# MAIN.net
KiCad netlist of a schematic drawn in Altium Designer
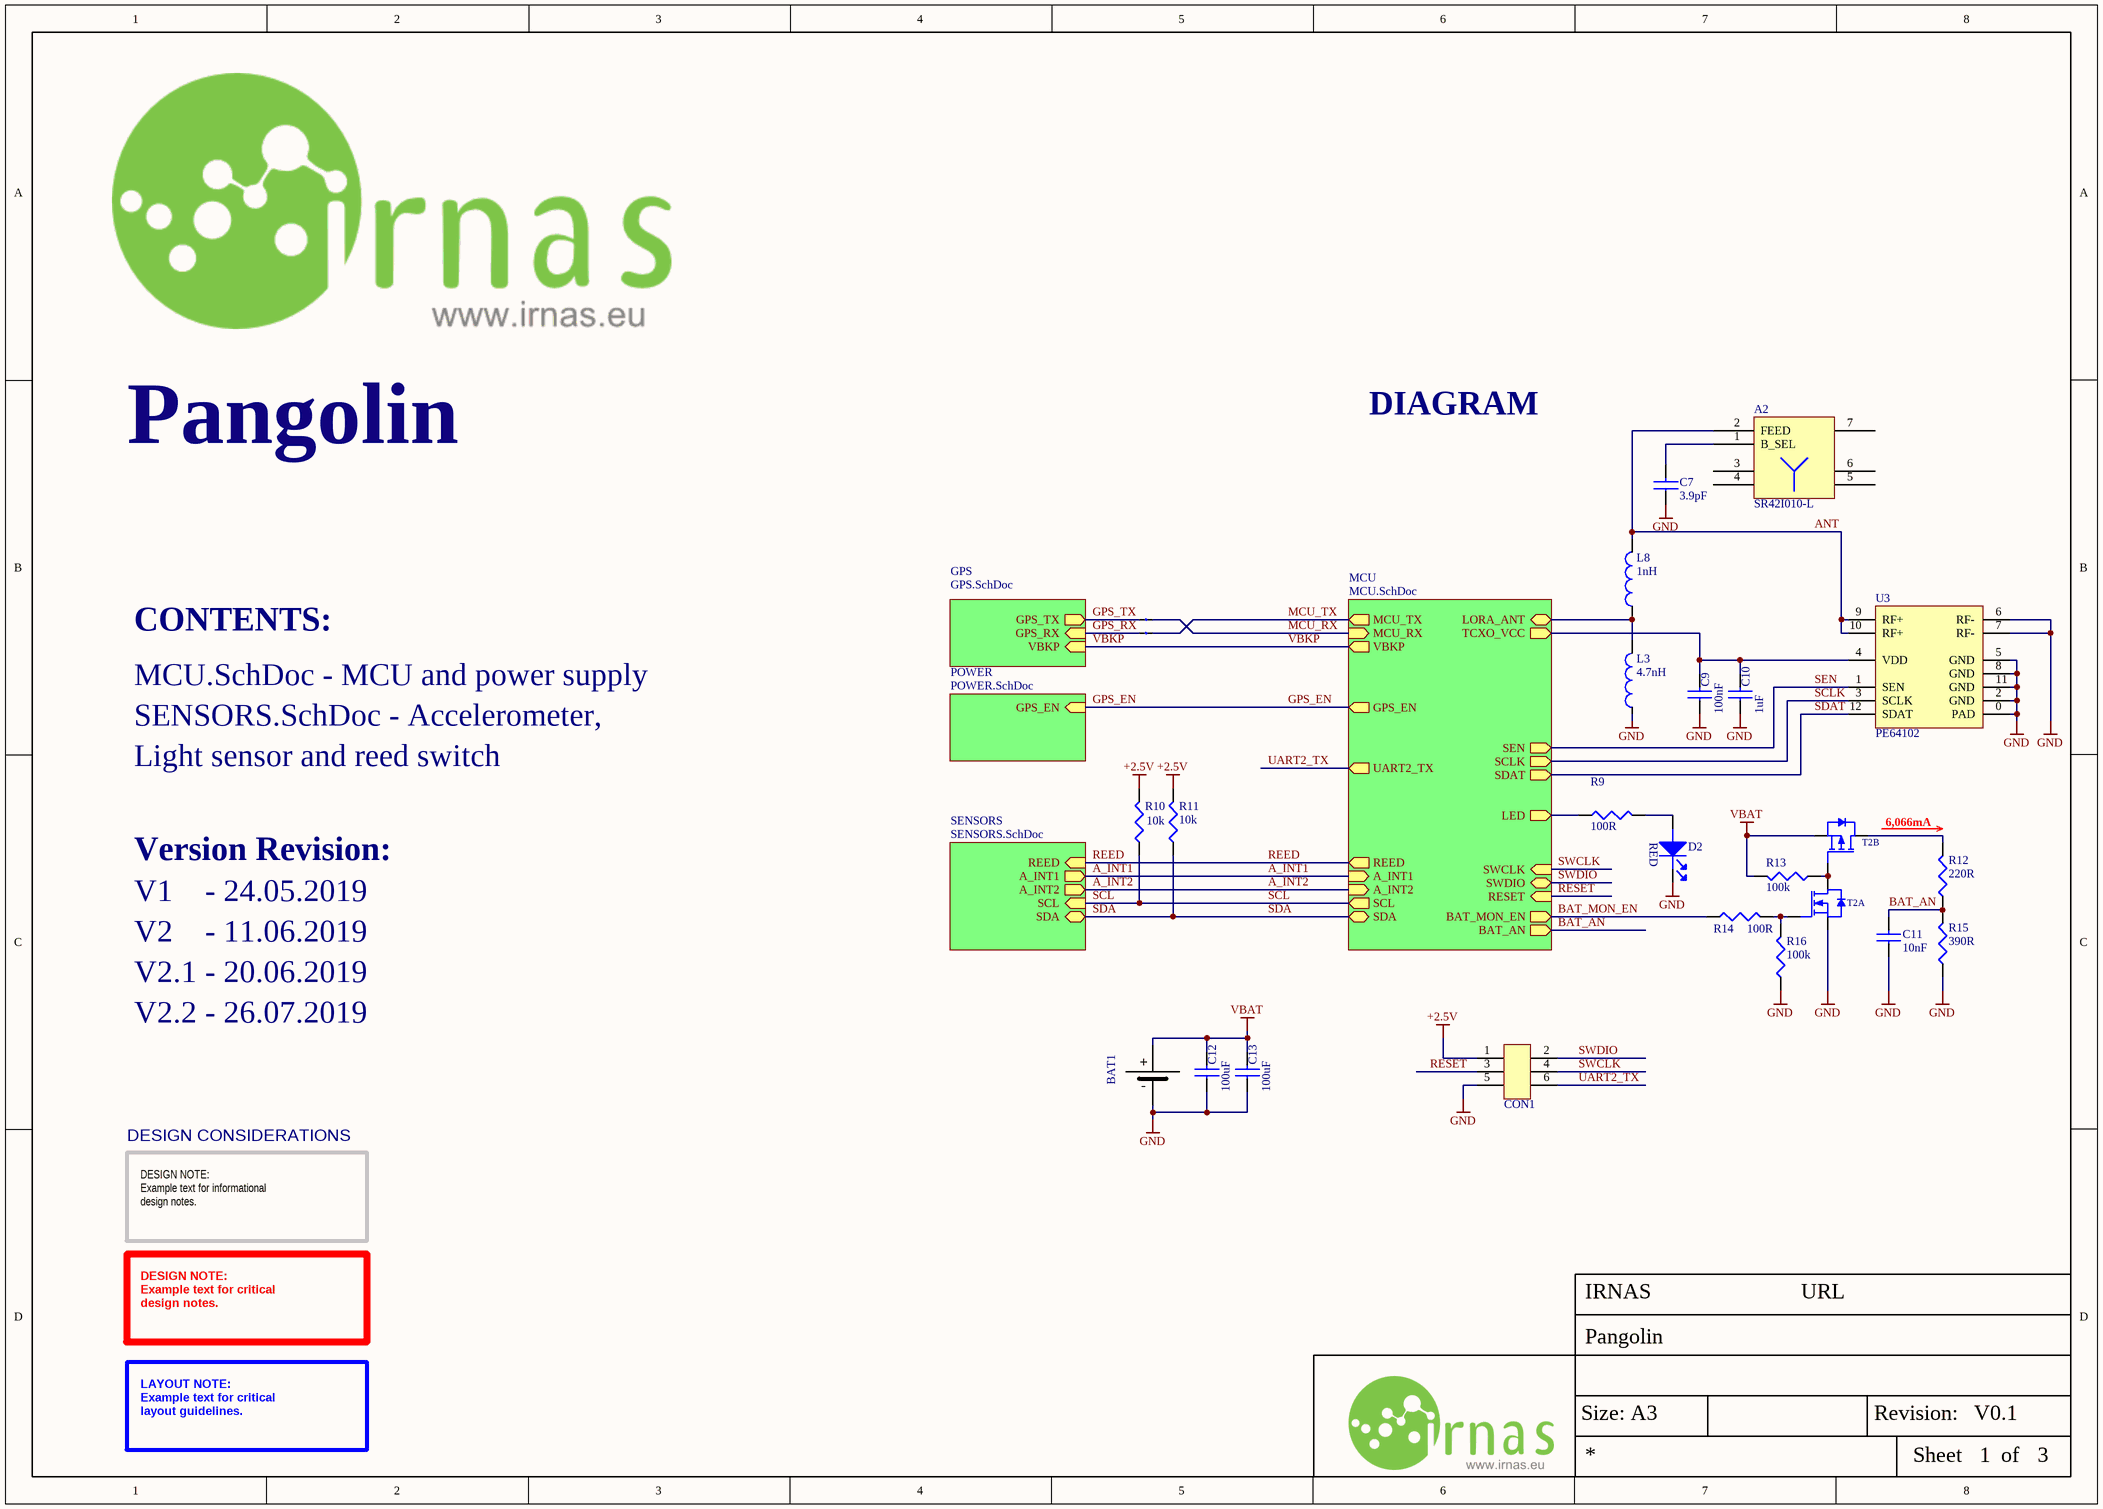
[diagram p0: MAIN.SchDoc]

(export (version "E")
  (design (tool "Eeschema 10.0.6"))
  (components
    (comp (ref "A2")
      (value "SR42I010-L")
      (footprint "SR42I010-L")
      (description "Antenna SMD -4dBi Gain 870MHz/928MHz Automotive 7-Pin SMD T/R")
      (fields (field (name "MANUFACTURER") "Antenova") (field (name "MANUFACTURER PART NUMBER") "SR42I010-R"))
      (libsource (lib "Passive") (part "ANT - SR42I010-L"))
    )
    (comp (ref "BAT1")
      (value "SAFT LS 14250PFR")
      (footprint "SAFT LS 14250PFR")
      (description "Battery: lithium; 3.6V; 1/2AA; 3pin,positive pole: 1pin; 1200mAh")
      (libsource (lib "Mechanical") (part "BAT - SAFT LS 14250PFR"))
    )
    (comp (ref "C7")
      (value "3.9pF")
      (footprint "CAP0402")
      (description "3.9 pF, 50 V, 0402 [1005 Metric], ± 0.25pF, NP0")
      (fields
        (field (name "MANUFACTURER") "KEMET")
        (field (name "MANUFACTURER PART NUMBER") "MC0402N3R9C500CT")
      )
      (libsource (lib "Passive") (part "C - 3.9pF/0402"))
    )
    (comp (ref "C9")
      (value "100nF")
      (footprint "CAP0402")
      (fields
        (field (name "MANUFACTURER") "Multicomp")
        (field (name "MANUFACTURER PART NUMBER") "MC0402X104J160CT")
        (field (name "TOLERANCE") "5%")
      )
      (libsource (lib "Passive") (part "C - 100nF/0402"))
    )
    (comp (ref "C10")
      (value "1uF")
      (footprint "CAP0402")
      (description "CAP CER 1UF 10V 20% X5R 0402")
      (fields
        (field (name "MANUFACTURER") "Murata")
        (field (name "MANUFACTURER PART NUMBER") "GRM155R61A105ME15D")
      )
      (libsource (lib "Passive") (part "C - 1uF/0402"))
    )
    (comp (ref "C11")
      (value "10nF")
      (footprint "CAP0402")
      (description "CAP CER 10000PF 16V X7R 0402")
      (fields
        (field (name "MANUFACTURER") "Murata")
        (field (name "MANUFACTURER PART NUMBER") "GRM155R71C103KA01D")
      )
      (libsource (lib "Passive") (part "C - 10nF/0402"))
    )
    (comp (ref "C12")
      (value "100uF")
      (footprint "CAP0805")
      (description "Multilayer Ceramic Capacitors MLCC - SMD/SMT 0805 100uF 4volts *Derate Voltage/Temp")
      (fields
        (field (name "MANUFACTURER") "Murata")
        (field (name "MANUFACTURER PART NUMBER") "GRM21BR60G107ME15L")
      )
      (libsource (lib "Passive") (part "C - 100uF/0805"))
    )
    (comp (ref "C13")
      (value "100uF")
      (footprint "CAP0805")
      (description "Multilayer Ceramic Capacitors MLCC - SMD/SMT 0805 100uF 4volts *Derate Voltage/Temp")
      (fields
        (field (name "MANUFACTURER") "Murata")
        (field (name "MANUFACTURER PART NUMBER") "GRM21BR60G107ME15L")
      )
      (libsource (lib "Passive") (part "C - 100uF/0805"))
    )
    (comp (ref "CON1")
      (value "Tag connect")
      (footprint "TC2030-IDC-NL")
      (libsource (lib "Connectors") (part "tag connecot 6 pin"))
    )
    (comp (ref "D2")
      (value "LED RED")
      (footprint "LED0603")
      (description "BROADCOM LIMITED - HSMS-C190 - LED, RED, 10MCD, 626NM")
      (fields
        (field (name "MANUFACTURER") "BROADCOM LIMITED")
        (field (name "MANUFACTURER PART NUMBER") "HSMS-C190")
      )
      (libsource (lib "Active") (part "LED - LED RED"))
    )
    (comp (ref "L3")
      (value "4.7nH")
      (footprint "IND0402")
      (description "Inductor RF Chip Multi-Layer 4.3nH 0.3nH 100MHz 8Q-Factor Air 300mA 210mOhm DCR 0402 Paper T/R")
      (fields
        (field (name "MANUFACTURER") "Murata")
        (field (name "MANUFACTURER PART NUMBER") "LQG15HN4N3S02D")
      )
      (libsource (lib "Passive") (part "L - 4.3nH/0402"))
    )
    (comp (ref "L8")
      (value "1nH")
      (footprint "IND0402")
      (description "Inductor RF Chip Multi-Layer 4.3nH 0.3nH 100MHz 8Q-Factor Air 300mA 210mOhm DCR 0402 Paper T/R")
      (fields
        (field (name "MANUFACTURER") "Murata")
        (field (name "MANUFACTURER PART NUMBER") "LQG15HN4N3S02D")
      )
      (libsource (lib "Passive") (part "L - 4.3nH/0402"))
    )
    (comp (ref "NT1")
      (value "~")
      (footprint "2 PIN STARPOINT")
      (description "Starpoint")
      (libsource (lib "Passive") (part "NetTie"))
    )
    (comp (ref "NT2")
      (value "~")
      (footprint "2 PIN STARPOINT")
      (description "Starpoint")
      (libsource (lib "Passive") (part "NetTie"))
    )
    (comp (ref "R9")
      (value "100R")
      (footprint "RES0402")
      (fields
        (field (name "MANUFACTURER") "Multicomp")
        (field (name "MANUFACTURER PART NUMBER") "MCMR04X1000FTL")
        (field (name "TOLERANCE") "1%")
      )
      (libsource (lib "Passive") (part "R - 100R/0402"))
    )
    (comp (ref "R10")
      (value "10k")
      (footprint "RES0402")
      (fields
        (field (name "MANUFACTURER") "Multicomp")
        (field (name "MANUFACTURER PART NUMBER") "MCWR04X1002FTL")
        (field (name "TOLERANCE") "1%")
      )
      (libsource (lib "Passive") (part "R - 10k/0402"))
    )
    (comp (ref "R11")
      (value "10k")
      (footprint "RES0402")
      (fields
        (field (name "MANUFACTURER") "Multicomp")
        (field (name "MANUFACTURER PART NUMBER") "MCWR04X1002FTL")
        (field (name "TOLERANCE") "1%")
      )
      (libsource (lib "Passive") (part "R - 10k/0402"))
    )
    (comp (ref "R12")
      (value "220R")
      (footprint "RES0402")
      (description "SMD Chip Resistor, 0402 [1005 Metric], 220 ohm, CRCW e3 Series, 50 V, Thick Film, 63 mW")
      (fields (field (name "MANUFACTURER") "Multicomp") (field (name "IRNAS PART NO.") "/"))
      (libsource (lib "Passive") (part "R - 220R/0402"))
    )
    (comp (ref "R13")
      (value "100k")
      (footprint "RES0402")
      (description "MULTICOMP   MCWR04X1003FTL   RES, THICK FILM, 100KOHM, 1%, 0.0625W")
      (fields
        (field (name "MANUFACTURER") "Multicomp")
        (field (name "MANUFACTURER PART NUMBER") "MCWR04X1003FTL")
      )
      (libsource (lib "Passive") (part "R - 100k/0402"))
    )
    (comp (ref "R14")
      (value "100R")
      (footprint "RES0402")
      (fields
        (field (name "MANUFACTURER") "Multicomp")
        (field (name "MANUFACTURER PART NUMBER") "MCMR04X1000FTL")
        (field (name "TOLERANCE") "1%")
      )
      (libsource (lib "Passive") (part "R - 100R/0402"))
    )
    (comp (ref "R15")
      (value "390R")
      (footprint "RES0402")
      (description "SMD Chip Resistor, 0402 [1005 Metric], 390 ohm, MCWR Series, 50 V, Thick Film, 62.5 mW")
      (fields (field (name "MANUFACTURER") "Multicomp") (field (name "IRNAS PART NO.") "/"))
      (libsource (lib "Passive") (part "R - 390R/0402"))
    )
    (comp (ref "R16")
      (value "100k")
      (footprint "RES0402")
      (description "MULTICOMP   MCWR04X1003FTL   RES, THICK FILM, 100KOHM, 1%, 0.0625W")
      (fields
        (field (name "MANUFACTURER") "Multicomp")
        (field (name "MANUFACTURER PART NUMBER") "MCWR04X1003FTL")
      )
      (libsource (lib "Passive") (part "R - 100k/0402"))
    )
    (comp (ref "T2")
      (value "VT6M1T2CR")
      (footprint "VMT6")
      (description "Dual MOSFET, N and P Channel, 100 mA, 20 V, 2.5 ohm, 4.5 V, 1 V")
      (fields (field (name "AUTHOR") "Ciril Golob"))
      (libsource (lib "Active") (part "T_M - VT6M1T2CR"))
    )
    (comp (ref "U3")
      (value "PE64102")
      (footprint "QFN-12")
      (description "RF IC Digitally Tunable Capacitor General Purpose 100MHz ~ 3GHz SPI Interface 12-QFN (2x2)")
      (fields (field (name "MANUFACTURER") "u-blox") (field (name "MANUFACTURER PART NUMBER") "MAX-M8Q-0"))
      (libsource (lib "Active") (part "RF - PE64102"))
    )
  )
  (nets
    (net (code "1") (name "+2.5V") (class "Default")
      (node (ref "CON1") (pin "1") (pinfunction "1_1") (pintype "open_collector"))
      (node (ref "R10") (pin "2") (pinfunction "2_2") (pintype "passive"))
      (node (ref "R11") (pin "2") (pinfunction "2_2") (pintype "passive"))
    )
    (net (code "2") (name "/ANT") (class "Default")
      (node (ref "A2") (pin "2") (pinfunction "FEED_2") (pintype "passive"))
      (node (ref "L8") (pin "2") (pinfunction "2_2") (pintype "passive"))
      (node (ref "U3") (pin "10") (pinfunction "RF+_10") (pintype "passive"))
      (node (ref "U3") (pin "9") (pinfunction "RF+_9") (pintype "passive"))
    )
    (net (code "5") (name "/BAT_AN") (class "Default")
      (node (ref "C11") (pin "2") (pinfunction "2_2") (pintype "passive"))
      (node (ref "R12") (pin "1") (pinfunction "1_1") (pintype "passive"))
      (node (ref "R15") (pin "2") (pinfunction "2_2") (pintype "passive"))
    )
    (net (code "6") (name "/BAT_MON_EN") (class "Default")
      (node (ref "R14") (pin "1") (pinfunction "1_1") (pintype "passive"))
    )
    (net (code "8") (name "/GPS_RX") (class "Default") (node (ref "NT2") (pin "1") (pintype "passive")))
    (net (code "9") (name "/GPS_TX") (class "Default") (node (ref "NT1") (pin "1") (pintype "passive")))
    (net (code "10") (name "/LED") (class "Default")
      (node (ref "R9") (pin "1") (pinfunction "1_1") (pintype "passive"))
    )
    (net (code "11") (name "/LORA_ANT") (class "Default")
      (node (ref "L3") (pin "2") (pinfunction "2_2") (pintype "passive"))
      (node (ref "L8") (pin "1") (pinfunction "1_1") (pintype "passive"))
    )
    (net (code "12") (name "/MCU_RX") (class "Default") (node (ref "NT1") (pin "2") (pintype "passive")))
    (net (code "13") (name "/MCU_TX") (class "Default") (node (ref "NT2") (pin "2") (pintype "passive")))
    (net (code "15") (name "/RESET") (class "Default")
      (node (ref "CON1") (pin "3") (pinfunction "3_3") (pintype "open_collector"))
    )
    (net (code "16") (name "/SCL") (class "Default")
      (node (ref "R10") (pin "1") (pinfunction "1_1") (pintype "passive"))
    )
    (net (code "17") (name "/SCLK") (class "Default")
      (node (ref "U3") (pin "3") (pinfunction "SCLK_3") (pintype "passive"))
    )
    (net (code "18") (name "/SDA") (class "Default")
      (node (ref "R11") (pin "1") (pinfunction "1_1") (pintype "passive"))
    )
    (net (code "19") (name "/SDAT") (class "Default")
      (node (ref "U3") (pin "12") (pinfunction "SDAT_12") (pintype "passive"))
    )
    (net (code "20") (name "/SEN") (class "Default")
      (node (ref "U3") (pin "1") (pinfunction "SEN_1") (pintype "passive"))
    )
    (net (code "21") (name "/SWCLK") (class "Default")
      (node (ref "CON1") (pin "4") (pinfunction "4_4") (pintype "open_collector"))
    )
    (net (code "22") (name "/SWDIO") (class "Default")
      (node (ref "CON1") (pin "2") (pinfunction "2_2") (pintype "open_collector"))
    )
    (net (code "23") (name "/TCXO_VCC") (class "Default")
      (node (ref "C10") (pin "2") (pinfunction "2_2") (pintype "passive"))
      (node (ref "C9") (pin "2") (pinfunction "2_2") (pintype "passive"))
      (node (ref "U3") (pin "4") (pinfunction "VDD_4") (pintype "passive"))
    )
    (net (code "24") (name "/UART2_TX") (class "Default")
      (node (ref "CON1") (pin "6") (pinfunction "6_6") (pintype "passive"))
    )
    (net (code "26") (name "GND") (class "Default")
      (node (ref "BAT1") (pin "1") (pinfunction "Negative_1") (pintype "passive"))
      (node (ref "C10") (pin "1") (pinfunction "1_1") (pintype "passive"))
      (node (ref "C11") (pin "1") (pinfunction "1_1") (pintype "passive"))
      (node (ref "C12") (pin "1") (pinfunction "1_1") (pintype "passive"))
      (node (ref "C13") (pin "1") (pinfunction "1_1") (pintype "passive"))
      (node (ref "C7") (pin "1") (pinfunction "1_1") (pintype "passive"))
      (node (ref "C9") (pin "1") (pinfunction "1_1") (pintype "passive"))
      (node (ref "CON1") (pin "5") (pinfunction "5_5") (pintype "open_collector"))
      (node (ref "D2") (pin "1") (pinfunction "cathode_1") (pintype "passive"))
      (node (ref "L3") (pin "1") (pinfunction "1_1") (pintype "passive"))
      (node (ref "R15") (pin "1") (pinfunction "1_1") (pintype "passive"))
      (node (ref "R16") (pin "1") (pinfunction "1_1") (pintype "passive"))
      (node (ref "T2") (pin "1") (pinfunction "S1_1") (pintype "passive"))
      (node (ref "U3") (pin "0") (pinfunction "PAD_0") (pintype "passive"))
      (node (ref "U3") (pin "11") (pinfunction "GND_11") (pintype "passive"))
      (node (ref "U3") (pin "2") (pinfunction "GND_2") (pintype "passive"))
      (node (ref "U3") (pin "5") (pinfunction "GND_5") (pintype "passive"))
      (node (ref "U3") (pin "6") (pinfunction "RF-_6") (pintype "passive"))
      (node (ref "U3") (pin "7") (pinfunction "RF-_7") (pintype "passive"))
      (node (ref "U3") (pin "8") (pinfunction "GND_8") (pintype "passive"))
    )
    (net (code "27") (name "Net-(A2-B_SEL)") (class "Default")
      (node (ref "A2") (pin "1") (pinfunction "B_SEL_1") (pintype "passive"))
      (node (ref "C7") (pin "2") (pinfunction "2_2") (pintype "passive"))
    )
    (net (code "28") (name "Net-(D2-ANODE)") (class "Default")
      (node (ref "D2") (pin "2") (pinfunction "ANODE_2") (pintype "passive"))
      (node (ref "R9") (pin "2") (pinfunction "2_2") (pintype "passive"))
    )
    (net (code "29") (name "Net-(T2A-D1)") (class "Default")
      (node (ref "R13") (pin "1") (pinfunction "1_1") (pintype "passive"))
      (node (ref "T2") (pin "5") (pinfunction "G2_5") (pintype "passive"))
      (node (ref "T2") (pin "6") (pinfunction "D1_6") (pintype "passive"))
    )
    (net (code "30") (name "Net-(T2A-G1)") (class "Default")
      (node (ref "R14") (pin "2") (pinfunction "2_2") (pintype "passive"))
      (node (ref "R16") (pin "2") (pinfunction "2_2") (pintype "passive"))
      (node (ref "T2") (pin "2") (pinfunction "G1_2") (pintype "passive"))
    )
    (net (code "31") (name "Net-(T2B-D2)") (class "Default")
      (node (ref "R12") (pin "2") (pinfunction "2_2") (pintype "passive"))
      (node (ref "T2") (pin "3") (pinfunction "D2_3") (pintype "passive"))
    )
    (net (code "32") (name "VBAT") (class "Default")
      (node (ref "BAT1") (pin "2") (pinfunction "Positive_2") (pintype "passive"))
      (node (ref "C12") (pin "2") (pinfunction "2_2") (pintype "passive"))
      (node (ref "C13") (pin "2") (pinfunction "2_2") (pintype "passive"))
      (node (ref "R13") (pin "2") (pinfunction "2_2") (pintype "passive"))
      (node (ref "T2") (pin "4") (pinfunction "S2_4") (pintype "passive"))
    )
    (net (code "33") (name "unconnected-(A2-Pad3)") (class "Default")
      (node (ref "A2") (pin "3") (pintype "passive"))
    )
    (net (code "34") (name "unconnected-(A2-Pad4)") (class "Default")
      (node (ref "A2") (pin "4") (pintype "passive"))
    )
    (net (code "35") (name "unconnected-(A2-Pad5)") (class "Default")
      (node (ref "A2") (pin "5") (pintype "passive"))
    )
    (net (code "36") (name "unconnected-(A2-Pad6)") (class "Default")
      (node (ref "A2") (pin "6") (pintype "passive"))
    )
    (net (code "37") (name "unconnected-(A2-Pad7)") (class "Default")
      (node (ref "A2") (pin "7") (pintype "passive"))
    )
  )
)
